# SCH_krunchcard_2025-07-19.net
KiCad netlist of a schematic drawn in EasyEDA
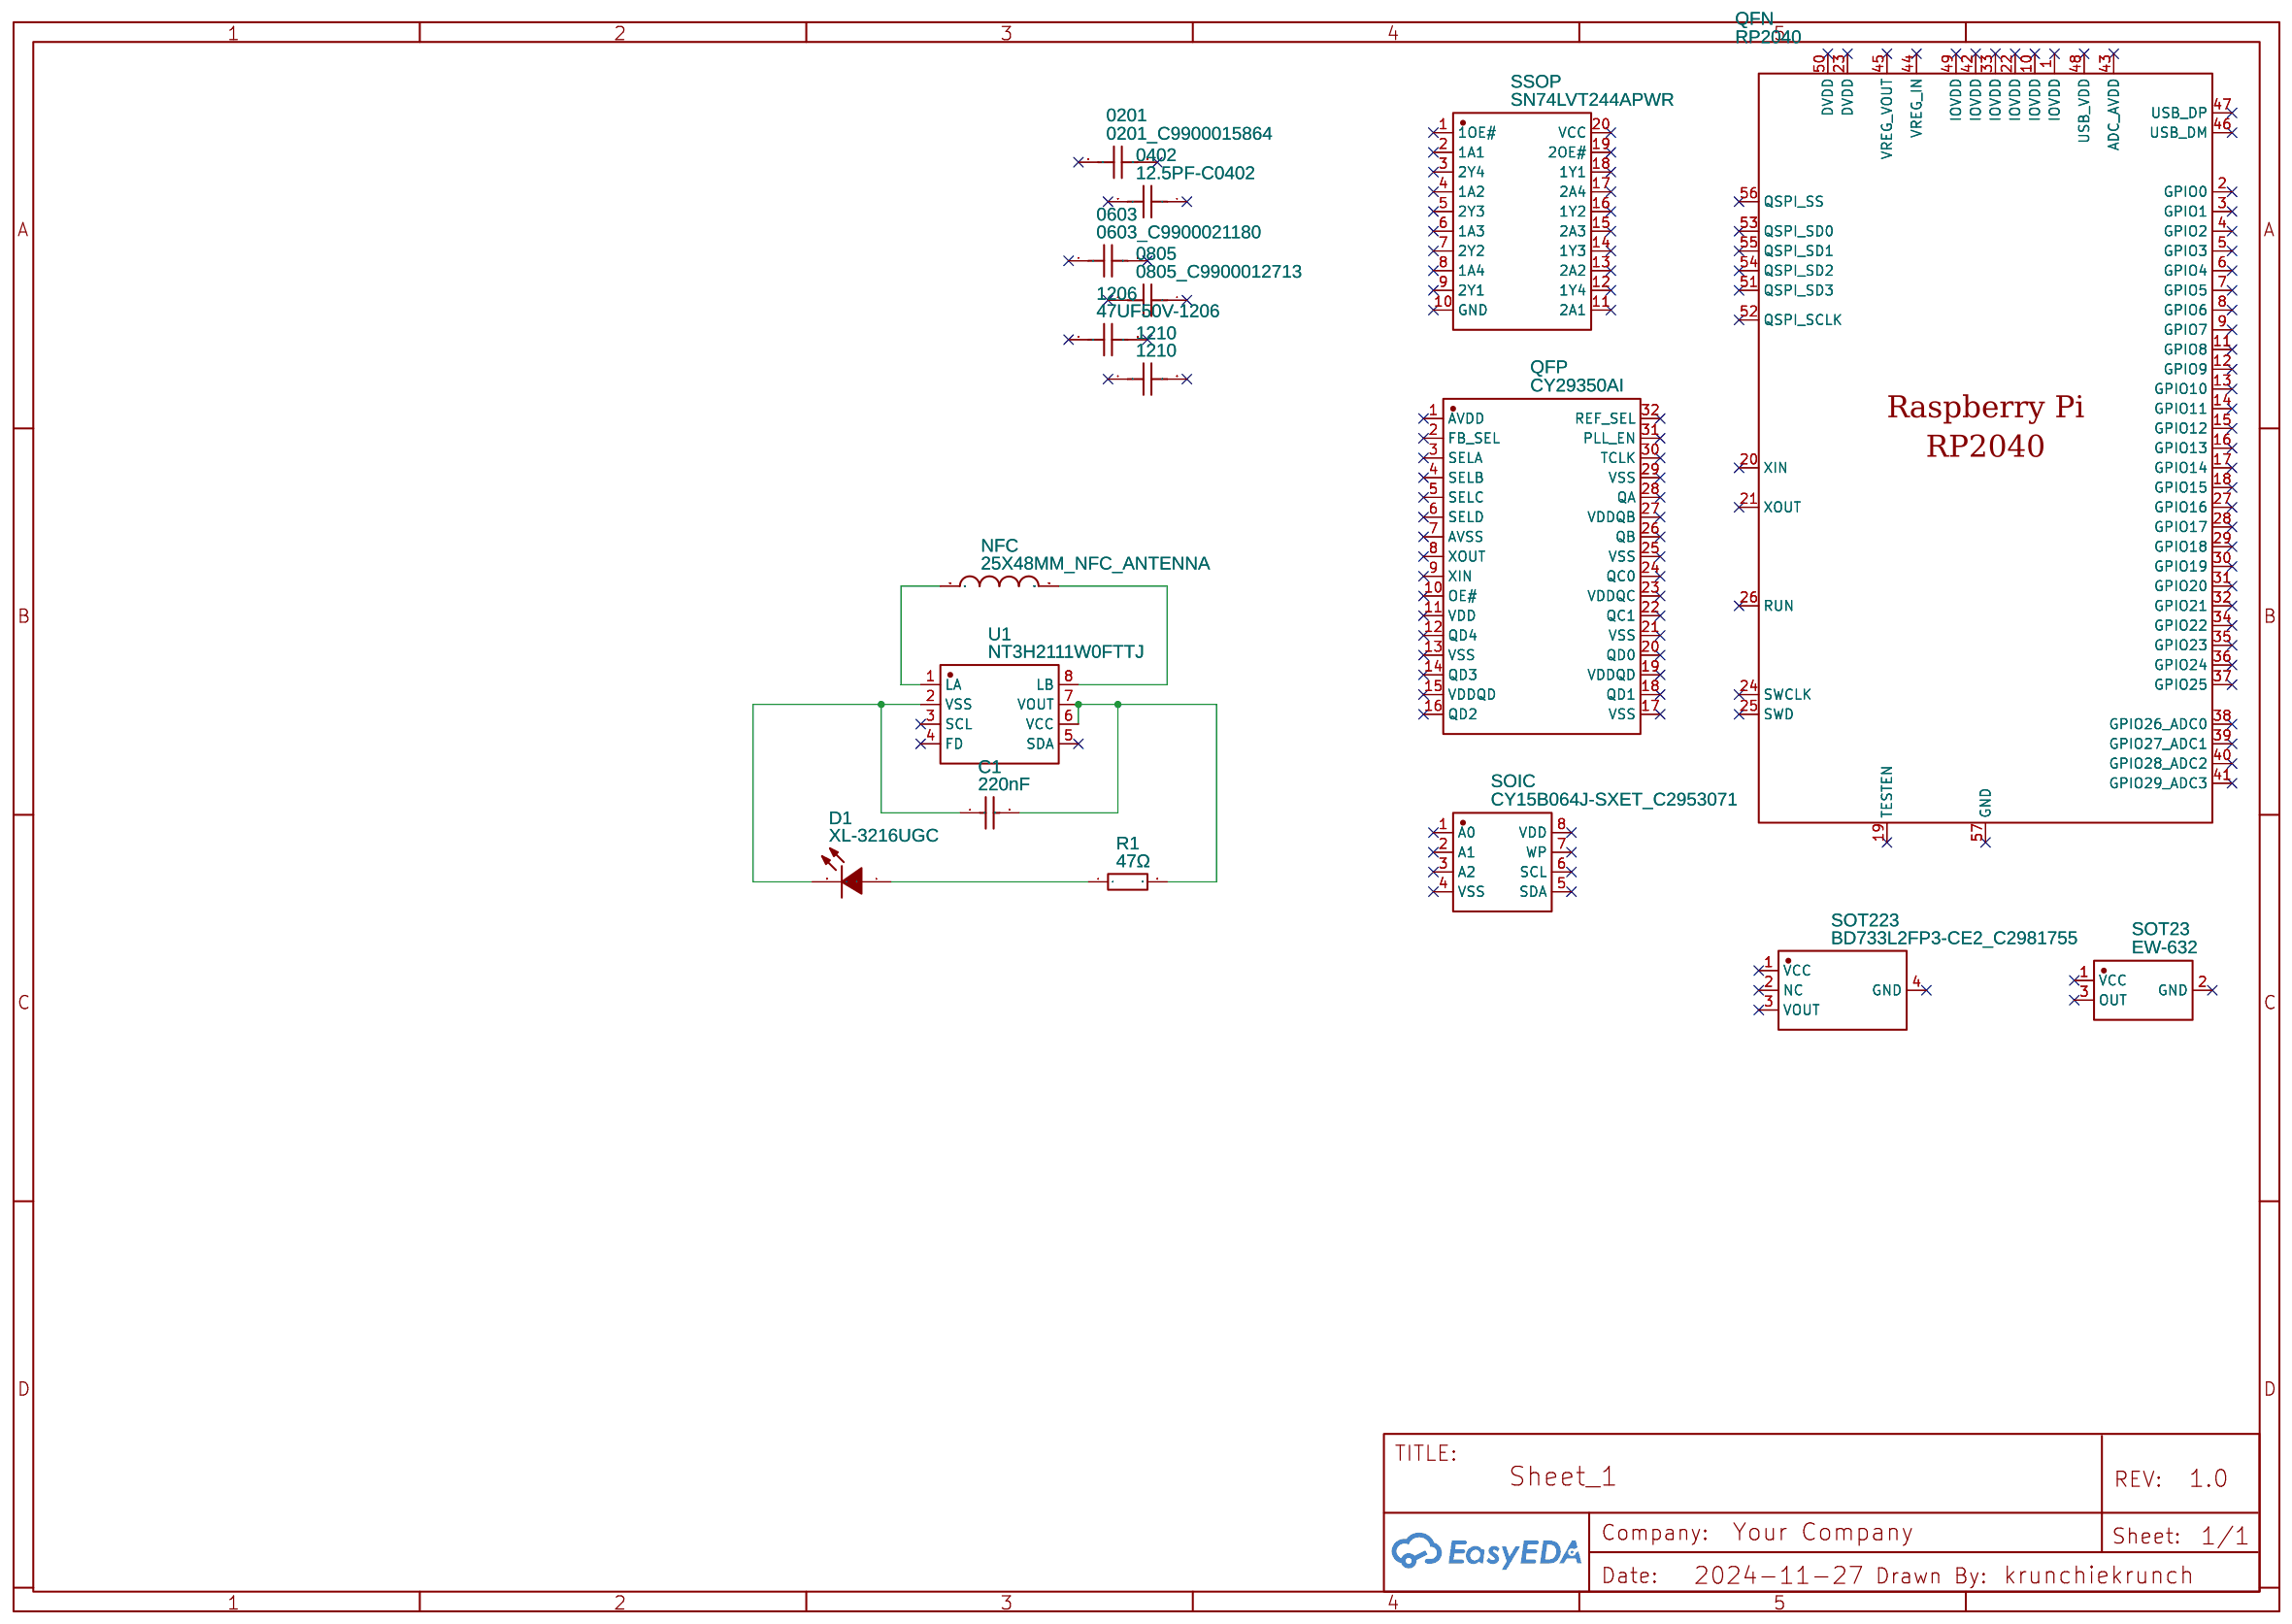
[diagram p0: schematic sheet]

(export (version "E")
  (design (tool "Eeschema 10.0.6"))
  (components
    (comp (ref "0201")
      (value "0201_C9900015864")
      (fields (field (name "Manufacturer Part") "0201"))
      (libsource (lib "") (part "0201_C9900015864"))
    )
    (comp (ref "0402")
      (value "12.5PF-C0402")
      (fields (field (name "Manufacturer Part") "12.5pF-C0402"))
      (libsource (lib "") (part "12.5PF-C0402"))
    )
    (comp (ref "0603")
      (value "0603_C9900021180")
      (fields (field (name "Manufacturer Part") "0603"))
      (libsource (lib "") (part "0603_C9900021180"))
    )
    (comp (ref "0805")
      (value "0805_C9900012713")
      (fields (field (name "Manufacturer Part") "0805"))
      (libsource (lib "") (part "0805_C9900012713"))
    )
    (comp (ref "1206")
      (value "47UF50V-1206")
      (fields (field (name "Manufacturer Part") "47uF50V-1206"))
      (libsource (lib "") (part "47UF50V-1206"))
    )
    (comp (ref "1210") (value "1210") (libsource (lib "") (part "1210")))
    (comp (ref "C1")
      (value "220nF")
      (fields
        (field (name "Manufacturer Part") "CC1206KKX7R9BB224")
        (field (name "Manufacturer") "YAGEO(国巨)")
      )
      (libsource (lib "") (part "CC1206KKX7R9BB224"))
    )
    (comp (ref "D1")
      (value "XL-3216UGC")
      (fields (field (name "Manufacturer") "XINGLIGHT(成兴光)"))
      (libsource (lib "") (part "XL-3216UGC"))
    )
    (comp (ref "NFC") (value "25X48MM_NFC_ANTENNA") (libsource (lib "") (part "25X48MM_NFC_ANTENNA")))
    (comp (ref "QFN")
      (value "RP2040")
      (fields (field (name "Manufacturer") "Raspberry Pi(树莓派)"))
      (libsource (lib "") (part "RP2040"))
    )
    (comp (ref "QFP")
      (value "CY29350AI")
      (fields (field (name "Manufacturer") "CYPRESS(赛普拉斯)"))
      (libsource (lib "") (part "CY29350AI"))
    )
    (comp (ref "R1")
      (value "47Ω")
      (fields (field (name "Manufacturer Part") "RS-06K470JT") (field (name "Manufacturer") "FH(风华)"))
      (libsource (lib "") (part "RS-06K470JT"))
    )
    (comp (ref "SOIC")
      (value "CY15B064J-SXET_C2953071")
      (fields
        (field (name "Manufacturer Part") "CY15B064J-SXET")
        (field (name "Manufacturer") "CYPRESS(赛普拉斯)")
      )
      (libsource (lib "") (part "CY15B064J-SXET_C2953071"))
    )
    (comp (ref "SOT23") (value "EW-632") (libsource (lib "") (part "EW-632")))
    (comp (ref "SOT223")
      (value "BD733L2FP3-CE2_C2981755")
      (fields (field (name "Manufacturer Part") "BD733L2FP3-CE2") (field (name "Manufacturer") "ROHM(罗姆)"))
      (libsource (lib "") (part "BD733L2FP3-CE2_C2981755"))
    )
    (comp (ref "SSOP")
      (value "SN74LVT244APWR")
      (fields (field (name "Manufacturer") "TI(德州仪器)"))
      (libsource (lib "") (part "SN74LVT244APWR"))
    )
    (comp (ref "U1")
      (value "NT3H2111W0FTTJ")
      (fields (field (name "Manufacturer") "NXP(恩智浦)"))
      (libsource (lib "") (part "NT3H2111W0FTTJ"))
    )
  )
  (nets
    (net (code "1") (name "Net-(D1-A)") (class "Default")
      (node (ref "D1") (pin "1") (pinfunction "A_1") (pintype "unspecified"))
      (node (ref "R1") (pin "1") (pinfunction "1_1") (pintype "input"))
    )
    (net (code "2") (name "Net-(D1-K)") (class "Default")
      (node (ref "C1") (pin "1") (pinfunction "1_1") (pintype "input"))
      (node (ref "D1") (pin "2") (pinfunction "K_2") (pintype "unspecified"))
      (node (ref "U1") (pin "2") (pinfunction "VSS_2") (pintype "unspecified"))
    )
    (net (code "3") (name "Net-(U1-LA)") (class "Default")
      (node (ref "NFC") (pin "P$1") (pinfunction "P$1_P$1") (pintype "bidirectional"))
      (node (ref "U1") (pin "1") (pinfunction "LA_1") (pintype "unspecified"))
    )
    (net (code "4") (name "Net-(U1-LB)") (class "Default")
      (node (ref "NFC") (pin "P$2") (pinfunction "P$2_P$2") (pintype "bidirectional"))
      (node (ref "U1") (pin "8") (pinfunction "LB_8") (pintype "unspecified"))
    )
    (net (code "5") (name "Net-(U1-VCC)") (class "Default")
      (node (ref "C1") (pin "2") (pinfunction "2_2") (pintype "input"))
      (node (ref "R1") (pin "2") (pinfunction "2_2") (pintype "input"))
      (node (ref "U1") (pin "6") (pinfunction "VCC_6") (pintype "unspecified"))
      (node (ref "U1") (pin "7") (pinfunction "VOUT_7") (pintype "unspecified"))
    )
    (net (code "6") (name "unconnected-(0201-Pad1)") (class "Default")
      (node (ref "0201") (pin "1") (pinfunction "1_1") (pintype "unspecified+no_connect"))
    )
    (net (code "7") (name "unconnected-(0201-Pad2)") (class "Default")
      (node (ref "0201") (pin "2") (pinfunction "2_2") (pintype "unspecified+no_connect"))
    )
    (net (code "8") (name "unconnected-(0402-Pad1)") (class "Default")
      (node (ref "0402") (pin "1") (pinfunction "1_1") (pintype "unspecified+no_connect"))
    )
    (net (code "9") (name "unconnected-(0402-Pad2)") (class "Default")
      (node (ref "0402") (pin "2") (pinfunction "2_2") (pintype "unspecified+no_connect"))
    )
    (net (code "10") (name "unconnected-(0603-Pad1)") (class "Default")
      (node (ref "0603") (pin "1") (pinfunction "1_1") (pintype "unspecified+no_connect"))
    )
    (net (code "11") (name "unconnected-(0603-Pad2)") (class "Default")
      (node (ref "0603") (pin "2") (pinfunction "2_2") (pintype "unspecified+no_connect"))
    )
    (net (code "12") (name "unconnected-(0805-Pad1)") (class "Default")
      (node (ref "0805") (pin "1") (pinfunction "1_1") (pintype "unspecified+no_connect"))
    )
    (net (code "13") (name "unconnected-(0805-Pad2)") (class "Default")
      (node (ref "0805") (pin "2") (pinfunction "2_2") (pintype "unspecified+no_connect"))
    )
    (net (code "14") (name "unconnected-(1206-Pad1)") (class "Default")
      (node (ref "1206") (pin "1") (pinfunction "1_1") (pintype "unspecified+no_connect"))
    )
    (net (code "15") (name "unconnected-(1206-Pad2)") (class "Default")
      (node (ref "1206") (pin "2") (pinfunction "2_2") (pintype "unspecified+no_connect"))
    )
    (net (code "16") (name "unconnected-(1210-Pad1)") (class "Default")
      (node (ref "1210") (pin "1") (pinfunction "1_1") (pintype "unspecified+no_connect"))
    )
    (net (code "17") (name "unconnected-(1210-Pad2)") (class "Default")
      (node (ref "1210") (pin "2") (pinfunction "2_2") (pintype "unspecified+no_connect"))
    )
    (net (code "18") (name "unconnected-(QFN-ADC_AVDD-Pad43)") (class "Default")
      (node (ref "QFN") (pin "43") (pinfunction "ADC_AVDD_43") (pintype "bidirectional+no_connect"))
    )
    (net (code "19") (name "unconnected-(QFN-DVDD-Pad23)") (class "Default")
      (node (ref "QFN") (pin "23") (pinfunction "DVDD_23") (pintype "bidirectional+no_connect"))
    )
    (net (code "20") (name "unconnected-(QFN-DVDD-Pad50)") (class "Default")
      (node (ref "QFN") (pin "50") (pinfunction "DVDD_50") (pintype "bidirectional+no_connect"))
    )
    (net (code "21") (name "unconnected-(QFN-GND-Pad57)") (class "Default")
      (node (ref "QFN") (pin "57") (pinfunction "GND_57") (pintype "bidirectional+no_connect"))
    )
    (net (code "22") (name "unconnected-(QFN-GPIO0-Pad2)") (class "Default")
      (node (ref "QFN") (pin "2") (pinfunction "GPIO0_2") (pintype "bidirectional+no_connect"))
    )
    (net (code "23") (name "unconnected-(QFN-GPIO1-Pad3)") (class "Default")
      (node (ref "QFN") (pin "3") (pinfunction "GPIO1_3") (pintype "bidirectional+no_connect"))
    )
    (net (code "24") (name "unconnected-(QFN-GPIO2-Pad4)") (class "Default")
      (node (ref "QFN") (pin "4") (pinfunction "GPIO2_4") (pintype "bidirectional+no_connect"))
    )
    (net (code "25") (name "unconnected-(QFN-GPIO3-Pad5)") (class "Default")
      (node (ref "QFN") (pin "5") (pinfunction "GPIO3_5") (pintype "bidirectional+no_connect"))
    )
    (net (code "26") (name "unconnected-(QFN-GPIO4-Pad6)") (class "Default")
      (node (ref "QFN") (pin "6") (pinfunction "GPIO4_6") (pintype "bidirectional+no_connect"))
    )
    (net (code "27") (name "unconnected-(QFN-GPIO5-Pad7)") (class "Default")
      (node (ref "QFN") (pin "7") (pinfunction "GPIO5_7") (pintype "bidirectional+no_connect"))
    )
    (net (code "28") (name "unconnected-(QFN-GPIO6-Pad8)") (class "Default")
      (node (ref "QFN") (pin "8") (pinfunction "GPIO6_8") (pintype "bidirectional+no_connect"))
    )
    (net (code "29") (name "unconnected-(QFN-GPIO7-Pad9)") (class "Default")
      (node (ref "QFN") (pin "9") (pinfunction "GPIO7_9") (pintype "bidirectional+no_connect"))
    )
    (net (code "30") (name "unconnected-(QFN-GPIO8-Pad11)") (class "Default")
      (node (ref "QFN") (pin "11") (pinfunction "GPIO8_11") (pintype "bidirectional+no_connect"))
    )
    (net (code "31") (name "unconnected-(QFN-GPIO9-Pad12)") (class "Default")
      (node (ref "QFN") (pin "12") (pinfunction "GPIO9_12") (pintype "bidirectional+no_connect"))
    )
    (net (code "32") (name "unconnected-(QFN-GPIO10-Pad13)") (class "Default")
      (node (ref "QFN") (pin "13") (pinfunction "GPIO10_13") (pintype "bidirectional+no_connect"))
    )
    (net (code "33") (name "unconnected-(QFN-GPIO11-Pad14)") (class "Default")
      (node (ref "QFN") (pin "14") (pinfunction "GPIO11_14") (pintype "bidirectional+no_connect"))
    )
    (net (code "34") (name "unconnected-(QFN-GPIO12-Pad15)") (class "Default")
      (node (ref "QFN") (pin "15") (pinfunction "GPIO12_15") (pintype "bidirectional+no_connect"))
    )
    (net (code "35") (name "unconnected-(QFN-GPIO13-Pad16)") (class "Default")
      (node (ref "QFN") (pin "16") (pinfunction "GPIO13_16") (pintype "bidirectional+no_connect"))
    )
    (net (code "36") (name "unconnected-(QFN-GPIO14-Pad17)") (class "Default")
      (node (ref "QFN") (pin "17") (pinfunction "GPIO14_17") (pintype "bidirectional+no_connect"))
    )
    (net (code "37") (name "unconnected-(QFN-GPIO15-Pad18)") (class "Default")
      (node (ref "QFN") (pin "18") (pinfunction "GPIO15_18") (pintype "bidirectional+no_connect"))
    )
    (net (code "38") (name "unconnected-(QFN-GPIO16-Pad27)") (class "Default")
      (node (ref "QFN") (pin "27") (pinfunction "GPIO16_27") (pintype "bidirectional+no_connect"))
    )
    (net (code "39") (name "unconnected-(QFN-GPIO17-Pad28)") (class "Default")
      (node (ref "QFN") (pin "28") (pinfunction "GPIO17_28") (pintype "bidirectional+no_connect"))
    )
    (net (code "40") (name "unconnected-(QFN-GPIO18-Pad29)") (class "Default")
      (node (ref "QFN") (pin "29") (pinfunction "GPIO18_29") (pintype "bidirectional+no_connect"))
    )
    (net (code "41") (name "unconnected-(QFN-GPIO19-Pad30)") (class "Default")
      (node (ref "QFN") (pin "30") (pinfunction "GPIO19_30") (pintype "bidirectional+no_connect"))
    )
    (net (code "42") (name "unconnected-(QFN-GPIO20-Pad31)") (class "Default")
      (node (ref "QFN") (pin "31") (pinfunction "GPIO20_31") (pintype "bidirectional+no_connect"))
    )
    (net (code "43") (name "unconnected-(QFN-GPIO21-Pad32)") (class "Default")
      (node (ref "QFN") (pin "32") (pinfunction "GPIO21_32") (pintype "bidirectional+no_connect"))
    )
    (net (code "44") (name "unconnected-(QFN-GPIO22-Pad34)") (class "Default")
      (node (ref "QFN") (pin "34") (pinfunction "GPIO22_34") (pintype "bidirectional+no_connect"))
    )
    (net (code "45") (name "unconnected-(QFN-GPIO23-Pad35)") (class "Default")
      (node (ref "QFN") (pin "35") (pinfunction "GPIO23_35") (pintype "bidirectional+no_connect"))
    )
    (net (code "46") (name "unconnected-(QFN-GPIO24-Pad36)") (class "Default")
      (node (ref "QFN") (pin "36") (pinfunction "GPIO24_36") (pintype "bidirectional+no_connect"))
    )
    (net (code "47") (name "unconnected-(QFN-GPIO25-Pad37)") (class "Default")
      (node (ref "QFN") (pin "37") (pinfunction "GPIO25_37") (pintype "bidirectional+no_connect"))
    )
    (net (code "48") (name "unconnected-(QFN-GPIO26_ADC0-Pad38)") (class "Default")
      (node (ref "QFN") (pin "38") (pinfunction "GPIO26_ADC0_38") (pintype "bidirectional+no_connect"))
    )
    (net (code "49") (name "unconnected-(QFN-GPIO27_ADC1-Pad39)") (class "Default")
      (node (ref "QFN") (pin "39") (pinfunction "GPIO27_ADC1_39") (pintype "bidirectional+no_connect"))
    )
    (net (code "50") (name "unconnected-(QFN-GPIO28_ADC2-Pad40)") (class "Default")
      (node (ref "QFN") (pin "40") (pinfunction "GPIO28_ADC2_40") (pintype "bidirectional+no_connect"))
    )
    (net (code "51") (name "unconnected-(QFN-GPIO29_ADC3-Pad41)") (class "Default")
      (node (ref "QFN") (pin "41") (pinfunction "GPIO29_ADC3_41") (pintype "bidirectional+no_connect"))
    )
    (net (code "52") (name "unconnected-(QFN-IOVDD-Pad1)") (class "Default")
      (node (ref "QFN") (pin "1") (pinfunction "IOVDD_1") (pintype "bidirectional+no_connect"))
    )
    (net (code "53") (name "unconnected-(QFN-IOVDD-Pad10)") (class "Default")
      (node (ref "QFN") (pin "10") (pinfunction "IOVDD_10") (pintype "bidirectional+no_connect"))
    )
    (net (code "54") (name "unconnected-(QFN-IOVDD-Pad22)") (class "Default")
      (node (ref "QFN") (pin "22") (pinfunction "IOVDD_22") (pintype "bidirectional+no_connect"))
    )
    (net (code "55") (name "unconnected-(QFN-IOVDD-Pad33)") (class "Default")
      (node (ref "QFN") (pin "33") (pinfunction "IOVDD_33") (pintype "bidirectional+no_connect"))
    )
    (net (code "56") (name "unconnected-(QFN-IOVDD-Pad42)") (class "Default")
      (node (ref "QFN") (pin "42") (pinfunction "IOVDD_42") (pintype "bidirectional+no_connect"))
    )
    (net (code "57") (name "unconnected-(QFN-IOVDD-Pad49)") (class "Default")
      (node (ref "QFN") (pin "49") (pinfunction "IOVDD_49") (pintype "bidirectional+no_connect"))
    )
    (net (code "58") (name "unconnected-(QFN-QSPI_SCLK-Pad52)") (class "Default")
      (node (ref "QFN") (pin "52") (pinfunction "QSPI_SCLK_52") (pintype "output+no_connect"))
    )
    (net (code "59") (name "unconnected-(QFN-QSPI_SD0-Pad53)") (class "Default")
      (node (ref "QFN") (pin "53") (pinfunction "QSPI_SD0_53") (pintype "bidirectional+no_connect"))
    )
    (net (code "60") (name "unconnected-(QFN-QSPI_SD1-Pad55)") (class "Default")
      (node (ref "QFN") (pin "55") (pinfunction "QSPI_SD1_55") (pintype "bidirectional+no_connect"))
    )
    (net (code "61") (name "unconnected-(QFN-QSPI_SD2-Pad54)") (class "Default")
      (node (ref "QFN") (pin "54") (pinfunction "QSPI_SD2_54") (pintype "bidirectional+no_connect"))
    )
    (net (code "62") (name "unconnected-(QFN-QSPI_SD3-Pad51)") (class "Default")
      (node (ref "QFN") (pin "51") (pinfunction "QSPI_SD3_51") (pintype "bidirectional+no_connect"))
    )
    (net (code "63") (name "unconnected-(QFN-QSPI_SS-Pad56)") (class "Default")
      (node (ref "QFN") (pin "56") (pinfunction "QSPI_SS_56") (pintype "bidirectional+no_connect"))
    )
    (net (code "64") (name "unconnected-(QFN-RUN-Pad26)") (class "Default")
      (node (ref "QFN") (pin "26") (pinfunction "RUN_26") (pintype "input+no_connect"))
    )
    (net (code "65") (name "unconnected-(QFN-SWCLK-Pad24)") (class "Default")
      (node (ref "QFN") (pin "24") (pinfunction "SWCLK_24") (pintype "output+no_connect"))
    )
    (net (code "66") (name "unconnected-(QFN-SWD-Pad25)") (class "Default")
      (node (ref "QFN") (pin "25") (pinfunction "SWD_25") (pintype "bidirectional+no_connect"))
    )
    (net (code "67") (name "unconnected-(QFN-TESTEN-Pad19)") (class "Default")
      (node (ref "QFN") (pin "19") (pinfunction "TESTEN_19") (pintype "unspecified+no_connect"))
    )
    (net (code "68") (name "unconnected-(QFN-USB_DM-Pad46)") (class "Default")
      (node (ref "QFN") (pin "46") (pinfunction "USB_DM_46") (pintype "bidirectional+no_connect"))
    )
    (net (code "69") (name "unconnected-(QFN-USB_DP-Pad47)") (class "Default")
      (node (ref "QFN") (pin "47") (pinfunction "USB_DP_47") (pintype "bidirectional+no_connect"))
    )
    (net (code "70") (name "unconnected-(QFN-USB_VDD-Pad48)") (class "Default")
      (node (ref "QFN") (pin "48") (pinfunction "USB_VDD_48") (pintype "bidirectional+no_connect"))
    )
    (net (code "71") (name "unconnected-(QFN-VREG_IN-Pad44)") (class "Default")
      (node (ref "QFN") (pin "44") (pinfunction "VREG_IN_44") (pintype "bidirectional+no_connect"))
    )
    (net (code "72") (name "unconnected-(QFN-VREG_VOUT-Pad45)") (class "Default")
      (node (ref "QFN") (pin "45") (pinfunction "VREG_VOUT_45") (pintype "bidirectional+no_connect"))
    )
    (net (code "73") (name "unconnected-(QFN-XIN-Pad20)") (class "Default")
      (node (ref "QFN") (pin "20") (pinfunction "XIN_20") (pintype "input+no_connect"))
    )
    (net (code "74") (name "unconnected-(QFN-XOUT-Pad21)") (class "Default")
      (node (ref "QFN") (pin "21") (pinfunction "XOUT_21") (pintype "unspecified+no_connect"))
    )
    (net (code "75") (name "unconnected-(QFP-AVDD-Pad1)") (class "Default")
      (node (ref "QFP") (pin "1") (pinfunction "AVDD_1") (pintype "unspecified+no_connect"))
    )
    (net (code "76") (name "unconnected-(QFP-AVSS-Pad7)") (class "Default")
      (node (ref "QFP") (pin "7") (pinfunction "AVSS_7") (pintype "unspecified+no_connect"))
    )
    (net (code "77") (name "unconnected-(QFP-FB_SEL-Pad2)") (class "Default")
      (node (ref "QFP") (pin "2") (pinfunction "FB_SEL_2") (pintype "unspecified+no_connect"))
    )
    (net (code "78") (name "unconnected-(QFP-OE#-Pad10)") (class "Default")
      (node (ref "QFP") (pin "10") (pinfunction "OE#_10") (pintype "unspecified+no_connect"))
    )
    (net (code "79") (name "unconnected-(QFP-PLL_EN-Pad31)") (class "Default")
      (node (ref "QFP") (pin "31") (pinfunction "PLL_EN_31") (pintype "unspecified+no_connect"))
    )
    (net (code "80") (name "unconnected-(QFP-QA-Pad28)") (class "Default")
      (node (ref "QFP") (pin "28") (pinfunction "QA_28") (pintype "unspecified+no_connect"))
    )
    (net (code "81") (name "unconnected-(QFP-QB-Pad26)") (class "Default")
      (node (ref "QFP") (pin "26") (pinfunction "QB_26") (pintype "unspecified+no_connect"))
    )
    (net (code "82") (name "unconnected-(QFP-QC0-Pad24)") (class "Default")
      (node (ref "QFP") (pin "24") (pinfunction "QC0_24") (pintype "unspecified+no_connect"))
    )
    (net (code "83") (name "unconnected-(QFP-QC1-Pad22)") (class "Default")
      (node (ref "QFP") (pin "22") (pinfunction "QC1_22") (pintype "unspecified+no_connect"))
    )
    (net (code "84") (name "unconnected-(QFP-QD0-Pad20)") (class "Default")
      (node (ref "QFP") (pin "20") (pinfunction "QD0_20") (pintype "unspecified+no_connect"))
    )
    (net (code "85") (name "unconnected-(QFP-QD1-Pad18)") (class "Default")
      (node (ref "QFP") (pin "18") (pinfunction "QD1_18") (pintype "unspecified+no_connect"))
    )
    (net (code "86") (name "unconnected-(QFP-QD2-Pad16)") (class "Default")
      (node (ref "QFP") (pin "16") (pinfunction "QD2_16") (pintype "unspecified+no_connect"))
    )
    (net (code "87") (name "unconnected-(QFP-QD3-Pad14)") (class "Default")
      (node (ref "QFP") (pin "14") (pinfunction "QD3_14") (pintype "unspecified+no_connect"))
    )
    (net (code "88") (name "unconnected-(QFP-QD4-Pad12)") (class "Default")
      (node (ref "QFP") (pin "12") (pinfunction "QD4_12") (pintype "unspecified+no_connect"))
    )
    (net (code "89") (name "unconnected-(QFP-REF_SEL-Pad32)") (class "Default")
      (node (ref "QFP") (pin "32") (pinfunction "REF_SEL_32") (pintype "unspecified+no_connect"))
    )
    (net (code "90") (name "unconnected-(QFP-SELA-Pad3)") (class "Default")
      (node (ref "QFP") (pin "3") (pinfunction "SELA_3") (pintype "unspecified+no_connect"))
    )
    (net (code "91") (name "unconnected-(QFP-SELB-Pad4)") (class "Default")
      (node (ref "QFP") (pin "4") (pinfunction "SELB_4") (pintype "unspecified+no_connect"))
    )
    (net (code "92") (name "unconnected-(QFP-SELC-Pad5)") (class "Default")
      (node (ref "QFP") (pin "5") (pinfunction "SELC_5") (pintype "unspecified+no_connect"))
    )
    (net (code "93") (name "unconnected-(QFP-SELD-Pad6)") (class "Default")
      (node (ref "QFP") (pin "6") (pinfunction "SELD_6") (pintype "unspecified+no_connect"))
    )
    (net (code "94") (name "unconnected-(QFP-TCLK-Pad30)") (class "Default")
      (node (ref "QFP") (pin "30") (pinfunction "TCLK_30") (pintype "unspecified+no_connect"))
    )
    (net (code "95") (name "unconnected-(QFP-VDD-Pad11)") (class "Default")
      (node (ref "QFP") (pin "11") (pinfunction "VDD_11") (pintype "unspecified+no_connect"))
    )
    (net (code "96") (name "unconnected-(QFP-VDDQB-Pad27)") (class "Default")
      (node (ref "QFP") (pin "27") (pinfunction "VDDQB_27") (pintype "unspecified+no_connect"))
    )
    (net (code "97") (name "unconnected-(QFP-VDDQC-Pad23)") (class "Default")
      (node (ref "QFP") (pin "23") (pinfunction "VDDQC_23") (pintype "unspecified+no_connect"))
    )
    (net (code "98") (name "unconnected-(QFP-VDDQD-Pad15)") (class "Default")
      (node (ref "QFP") (pin "15") (pinfunction "VDDQD_15") (pintype "unspecified+no_connect"))
    )
    (net (code "99") (name "unconnected-(QFP-VDDQD-Pad19)") (class "Default")
      (node (ref "QFP") (pin "19") (pinfunction "VDDQD_19") (pintype "unspecified+no_connect"))
    )
    (net (code "100") (name "unconnected-(QFP-VSS-Pad13)") (class "Default")
      (node (ref "QFP") (pin "13") (pinfunction "VSS_13") (pintype "unspecified+no_connect"))
    )
    (net (code "101") (name "unconnected-(QFP-VSS-Pad17)") (class "Default")
      (node (ref "QFP") (pin "17") (pinfunction "VSS_17") (pintype "unspecified+no_connect"))
    )
    (net (code "102") (name "unconnected-(QFP-VSS-Pad21)") (class "Default")
      (node (ref "QFP") (pin "21") (pinfunction "VSS_21") (pintype "unspecified+no_connect"))
    )
    (net (code "103") (name "unconnected-(QFP-VSS-Pad25)") (class "Default")
      (node (ref "QFP") (pin "25") (pinfunction "VSS_25") (pintype "unspecified+no_connect"))
    )
    (net (code "104") (name "unconnected-(QFP-VSS-Pad29)") (class "Default")
      (node (ref "QFP") (pin "29") (pinfunction "VSS_29") (pintype "unspecified+no_connect"))
    )
    (net (code "105") (name "unconnected-(QFP-XIN-Pad9)") (class "Default")
      (node (ref "QFP") (pin "9") (pinfunction "XIN_9") (pintype "unspecified+no_connect"))
    )
    (net (code "106") (name "unconnected-(QFP-XOUT-Pad8)") (class "Default")
      (node (ref "QFP") (pin "8") (pinfunction "XOUT_8") (pintype "unspecified+no_connect"))
    )
    (net (code "107") (name "unconnected-(SOIC-A0-Pad1)") (class "Default")
      (node (ref "SOIC") (pin "1") (pinfunction "A0_1") (pintype "unspecified+no_connect"))
    )
    (net (code "108") (name "unconnected-(SOIC-A1-Pad2)") (class "Default")
      (node (ref "SOIC") (pin "2") (pinfunction "A1_2") (pintype "unspecified+no_connect"))
    )
    (net (code "109") (name "unconnected-(SOIC-A2-Pad3)") (class "Default")
      (node (ref "SOIC") (pin "3") (pinfunction "A2_3") (pintype "unspecified+no_connect"))
    )
    (net (code "110") (name "unconnected-(SOIC-SCL-Pad6)") (class "Default")
      (node (ref "SOIC") (pin "6") (pinfunction "SCL_6") (pintype "unspecified+no_connect"))
    )
    (net (code "111") (name "unconnected-(SOIC-SDA-Pad5)") (class "Default")
      (node (ref "SOIC") (pin "5") (pinfunction "SDA_5") (pintype "unspecified+no_connect"))
    )
    (net (code "112") (name "unconnected-(SOIC-VDD-Pad8)") (class "Default")
      (node (ref "SOIC") (pin "8") (pinfunction "VDD_8") (pintype "unspecified+no_connect"))
    )
    (net (code "113") (name "unconnected-(SOIC-VSS-Pad4)") (class "Default")
      (node (ref "SOIC") (pin "4") (pinfunction "VSS_4") (pintype "unspecified+no_connect"))
    )
    (net (code "114") (name "unconnected-(SOIC-WP-Pad7)") (class "Default")
      (node (ref "SOIC") (pin "7") (pinfunction "WP_7") (pintype "unspecified+no_connect"))
    )
    (net (code "115") (name "unconnected-(SOT23-GND-Pad2)") (class "Default")
      (node (ref "SOT23") (pin "2") (pinfunction "GND_2") (pintype "unspecified+no_connect"))
    )
    (net (code "116") (name "unconnected-(SOT23-OUT-Pad3)") (class "Default")
      (node (ref "SOT23") (pin "3") (pinfunction "OUT_3") (pintype "unspecified+no_connect"))
    )
    (net (code "117") (name "unconnected-(SOT23-VCC-Pad1)") (class "Default")
      (node (ref "SOT23") (pin "1") (pinfunction "VCC_1") (pintype "unspecified+no_connect"))
    )
    (net (code "118") (name "unconnected-(SOT223-GND-Pad4)") (class "Default")
      (node (ref "SOT223") (pin "4") (pinfunction "GND_4") (pintype "unspecified+no_connect"))
    )
    (net (code "119") (name "unconnected-(SOT223-NC-Pad2)") (class "Default")
      (node (ref "SOT223") (pin "2") (pinfunction "NC_2") (pintype "unspecified+no_connect"))
    )
    (net (code "120") (name "unconnected-(SOT223-VCC-Pad1)") (class "Default")
      (node (ref "SOT223") (pin "1") (pinfunction "VCC_1") (pintype "unspecified+no_connect"))
    )
    (net (code "121") (name "unconnected-(SOT223-VOUT-Pad3)") (class "Default")
      (node (ref "SOT223") (pin "3") (pinfunction "VOUT_3") (pintype "unspecified+no_connect"))
    )
    (net (code "122") (name "unconnected-(SSOP-1A1-Pad2)") (class "Default")
      (node (ref "SSOP") (pin "2") (pinfunction "1A1_2") (pintype "unspecified+no_connect"))
    )
    (net (code "123") (name "unconnected-(SSOP-1A2-Pad4)") (class "Default")
      (node (ref "SSOP") (pin "4") (pinfunction "1A2_4") (pintype "unspecified+no_connect"))
    )
    (net (code "124") (name "unconnected-(SSOP-1A3-Pad6)") (class "Default")
      (node (ref "SSOP") (pin "6") (pinfunction "1A3_6") (pintype "unspecified+no_connect"))
    )
    (net (code "125") (name "unconnected-(SSOP-1A4-Pad8)") (class "Default")
      (node (ref "SSOP") (pin "8") (pinfunction "1A4_8") (pintype "unspecified+no_connect"))
    )
    (net (code "126") (name "unconnected-(SSOP-1OE#-Pad1)") (class "Default")
      (node (ref "SSOP") (pin "1") (pinfunction "1OE#_1") (pintype "unspecified+no_connect"))
    )
    (net (code "127") (name "unconnected-(SSOP-1Y1-Pad18)") (class "Default")
      (node (ref "SSOP") (pin "18") (pinfunction "1Y1_18") (pintype "unspecified+no_connect"))
    )
    (net (code "128") (name "unconnected-(SSOP-1Y2-Pad16)") (class "Default")
      (node (ref "SSOP") (pin "16") (pinfunction "1Y2_16") (pintype "unspecified+no_connect"))
    )
    (net (code "129") (name "unconnected-(SSOP-1Y3-Pad14)") (class "Default")
      (node (ref "SSOP") (pin "14") (pinfunction "1Y3_14") (pintype "unspecified+no_connect"))
    )
    (net (code "130") (name "unconnected-(SSOP-1Y4-Pad12)") (class "Default")
      (node (ref "SSOP") (pin "12") (pinfunction "1Y4_12") (pintype "unspecified+no_connect"))
    )
    (net (code "131") (name "unconnected-(SSOP-2A1-Pad11)") (class "Default")
      (node (ref "SSOP") (pin "11") (pinfunction "2A1_11") (pintype "unspecified+no_connect"))
    )
    (net (code "132") (name "unconnected-(SSOP-2A2-Pad13)") (class "Default")
      (node (ref "SSOP") (pin "13") (pinfunction "2A2_13") (pintype "unspecified+no_connect"))
    )
    (net (code "133") (name "unconnected-(SSOP-2A3-Pad15)") (class "Default")
      (node (ref "SSOP") (pin "15") (pinfunction "2A3_15") (pintype "unspecified+no_connect"))
    )
    (net (code "134") (name "unconnected-(SSOP-2A4-Pad17)") (class "Default")
      (node (ref "SSOP") (pin "17") (pinfunction "2A4_17") (pintype "unspecified+no_connect"))
    )
    (net (code "135") (name "unconnected-(SSOP-2OE#-Pad19)") (class "Default")
      (node (ref "SSOP") (pin "19") (pinfunction "2OE#_19") (pintype "unspecified+no_connect"))
    )
    (net (code "136") (name "unconnected-(SSOP-2Y1-Pad9)") (class "Default")
      (node (ref "SSOP") (pin "9") (pinfunction "2Y1_9") (pintype "unspecified+no_connect"))
    )
    (net (code "137") (name "unconnected-(SSOP-2Y2-Pad7)") (class "Default")
      (node (ref "SSOP") (pin "7") (pinfunction "2Y2_7") (pintype "unspecified+no_connect"))
    )
    (net (code "138") (name "unconnected-(SSOP-2Y3-Pad5)") (class "Default")
      (node (ref "SSOP") (pin "5") (pinfunction "2Y3_5") (pintype "unspecified+no_connect"))
    )
    (net (code "139") (name "unconnected-(SSOP-2Y4-Pad3)") (class "Default")
      (node (ref "SSOP") (pin "3") (pinfunction "2Y4_3") (pintype "unspecified+no_connect"))
    )
    (net (code "140") (name "unconnected-(SSOP-GND-Pad10)") (class "Default")
      (node (ref "SSOP") (pin "10") (pinfunction "GND_10") (pintype "unspecified+no_connect"))
    )
    (net (code "141") (name "unconnected-(SSOP-VCC-Pad20)") (class "Default")
      (node (ref "SSOP") (pin "20") (pinfunction "VCC_20") (pintype "unspecified+no_connect"))
    )
    (net (code "142") (name "unconnected-(U1-FD-Pad4)") (class "Default")
      (node (ref "U1") (pin "4") (pinfunction "FD_4") (pintype "unspecified+no_connect"))
    )
    (net (code "143") (name "unconnected-(U1-SCL-Pad3)") (class "Default")
      (node (ref "U1") (pin "3") (pinfunction "SCL_3") (pintype "unspecified+no_connect"))
    )
    (net (code "144") (name "unconnected-(U1-SDA-Pad5)") (class "Default")
      (node (ref "U1") (pin "5") (pinfunction "SDA_5") (pintype "unspecified+no_connect"))
    )
  )
)
